# Control.net
KiCad netlist of a schematic drawn in Altium Designer
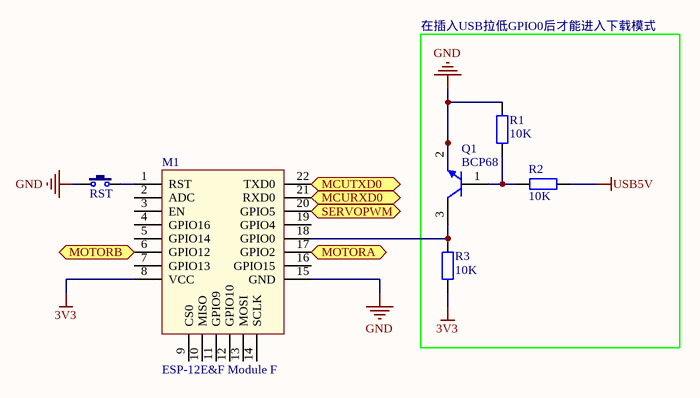
[diagram p0: Control.SchDoc]

(export (version "E")
  (design (tool "Eeschema 10.0.6"))
  (components
    (comp (ref "M1")
      (value "ESP-12E&F Module F")
      (footprint "ESP-12E&F Module")
      (description "ESP-12E&F Module")
      (libsource (lib "ESP-12E&F Module") (part "ESP-12E&F Module"))
    )
    (comp (ref "Q1")
      (value "BCP68")
      (footprint "SOT-23")
      (description "NPN三极管")
      (fields (field (name "PUBLISHER") "Altium Limited"))
      (libsource (lib "0.4 - 三极管") (part "BCP68"))
    )
    (comp (ref "R1")
      (value "10K")
      (footprint "R 0805_L")
      (description "贴片电阻")
      (fields (field (name "版权归属") "来自淘宝 ID：黄晶宝石"))
      (libsource (lib "0.1 - 电阻-电容-电感") (part "R"))
    )
    (comp (ref "R2")
      (value "10K")
      (footprint "R 0805_L")
      (description "贴片电阻")
      (fields (field (name "版权归属") "来自淘宝 ID：黄晶宝石"))
      (libsource (lib "0.1 - 电阻-电容-电感") (part "R"))
    )
    (comp (ref "R3")
      (value "10K")
      (footprint "R 0805_L")
      (description "贴片电阻")
      (fields (field (name "版权归属") "来自淘宝 ID：黄晶宝石"))
      (libsource (lib "0.1 - 电阻-电容-电感") (part "R"))
    )
    (comp (ref "RST")
      (value "3x6x5")
      (footprint "TSW SMD-3*6*2.5")
      (description "3x6轻触开关")
      (fields (field (name "版权归属") "封装库来自淘宝 ID：黄晶宝石"))
      (libsource (lib "0.7 - 常用按键-开关") (part "TSW 3x6"))
    )
  )
  (nets
    (net (code "1") (name "/MCURXD0") (class "Default")
      (node (ref "M1") (pin "21") (pinfunction "RXD0_21") (pintype "passive"))
    )
    (net (code "2") (name "/MCUTXD0") (class "Default")
      (node (ref "M1") (pin "22") (pinfunction "TXD0_22") (pintype "passive"))
    )
    (net (code "3") (name "/MOTORA") (class "Default")
      (node (ref "M1") (pin "17") (pinfunction "GPIO2_17") (pintype "passive"))
    )
    (net (code "4") (name "/MOTORB") (class "Default")
      (node (ref "M1") (pin "6") (pinfunction "GPIO12_6") (pintype "passive"))
    )
    (net (code "5") (name "/SERVOPWM") (class "Default")
      (node (ref "M1") (pin "20") (pinfunction "GPIO5_20") (pintype "passive"))
    )
    (net (code "6") (name "3V3") (class "Default")
      (node (ref "M1") (pin "8") (pinfunction "VCC_8") (pintype "passive"))
      (node (ref "R3") (pin "1") (pinfunction "1_1") (pintype "passive"))
    )
    (net (code "7") (name "GND") (class "Default")
      (node (ref "M1") (pin "15") (pinfunction "GND_15") (pintype "passive"))
      (node (ref "Q1") (pin "2") (pinfunction "E_2") (pintype "passive"))
      (node (ref "R1") (pin "2") (pinfunction "2_2") (pintype "passive"))
      (node (ref "RST") (pin "1") (pinfunction "1_1") (pintype "passive"))
    )
    (net (code "8") (name "Net-(M1-GPIO0)") (class "Default")
      (node (ref "M1") (pin "18") (pinfunction "GPIO0_18") (pintype "passive"))
      (node (ref "Q1") (pin "3") (pinfunction "C_3") (pintype "passive"))
      (node (ref "R3") (pin "2") (pinfunction "2_2") (pintype "passive"))
    )
    (net (code "9") (name "Net-(M1-RST)") (class "Default")
      (node (ref "M1") (pin "1") (pinfunction "RST_1") (pintype "passive"))
      (node (ref "RST") (pin "2") (pinfunction "2_2") (pintype "passive"))
    )
    (net (code "10") (name "Net-(Q1-B)") (class "Default")
      (node (ref "Q1") (pin "1") (pinfunction "B_1") (pintype "passive"))
      (node (ref "R1") (pin "1") (pinfunction "1_1") (pintype "passive"))
      (node (ref "R2") (pin "1") (pinfunction "1_1") (pintype "passive"))
    )
    (net (code "11") (name "USB5V") (class "Default")
      (node (ref "R2") (pin "2") (pinfunction "2_2") (pintype "passive"))
    )
    (net (code "12") (name "unconnected-(M1-ADC-Pad2)") (class "Default")
      (node (ref "M1") (pin "2") (pinfunction "ADC_2") (pintype "passive"))
    )
    (net (code "13") (name "unconnected-(M1-CS0-Pad9)") (class "Default")
      (node (ref "M1") (pin "9") (pinfunction "CS0_9") (pintype "passive"))
    )
    (net (code "14") (name "unconnected-(M1-EN-Pad3)") (class "Default")
      (node (ref "M1") (pin "3") (pinfunction "EN_3") (pintype "passive"))
    )
    (net (code "15") (name "unconnected-(M1-GPIO4-Pad19)") (class "Default")
      (node (ref "M1") (pin "19") (pinfunction "GPIO4_19") (pintype "passive"))
    )
    (net (code "16") (name "unconnected-(M1-GPIO9-Pad11)") (class "Default")
      (node (ref "M1") (pin "11") (pinfunction "GPIO9_11") (pintype "passive"))
    )
    (net (code "17") (name "unconnected-(M1-GPIO10-Pad12)") (class "Default")
      (node (ref "M1") (pin "12") (pinfunction "GPIO10_12") (pintype "passive"))
    )
    (net (code "18") (name "unconnected-(M1-GPIO13-Pad7)") (class "Default")
      (node (ref "M1") (pin "7") (pinfunction "GPIO13_7") (pintype "passive"))
    )
    (net (code "19") (name "unconnected-(M1-GPIO14-Pad5)") (class "Default")
      (node (ref "M1") (pin "5") (pinfunction "GPIO14_5") (pintype "passive"))
    )
    (net (code "20") (name "unconnected-(M1-GPIO15-Pad16)") (class "Default")
      (node (ref "M1") (pin "16") (pinfunction "GPIO15_16") (pintype "passive"))
    )
    (net (code "21") (name "unconnected-(M1-GPIO16-Pad4)") (class "Default")
      (node (ref "M1") (pin "4") (pinfunction "GPIO16_4") (pintype "passive"))
    )
    (net (code "22") (name "unconnected-(M1-MISO-Pad10)") (class "Default")
      (node (ref "M1") (pin "10") (pinfunction "MISO_10") (pintype "passive"))
    )
    (net (code "23") (name "unconnected-(M1-MOSI-Pad13)") (class "Default")
      (node (ref "M1") (pin "13") (pinfunction "MOSI_13") (pintype "passive"))
    )
    (net (code "24") (name "unconnected-(M1-SCLK-Pad14)") (class "Default")
      (node (ref "M1") (pin "14") (pinfunction "SCLK_14") (pintype "passive"))
    )
  )
)
